# Telemetry_receiver.net
KiCad netlist of a schematic drawn in EAGLE
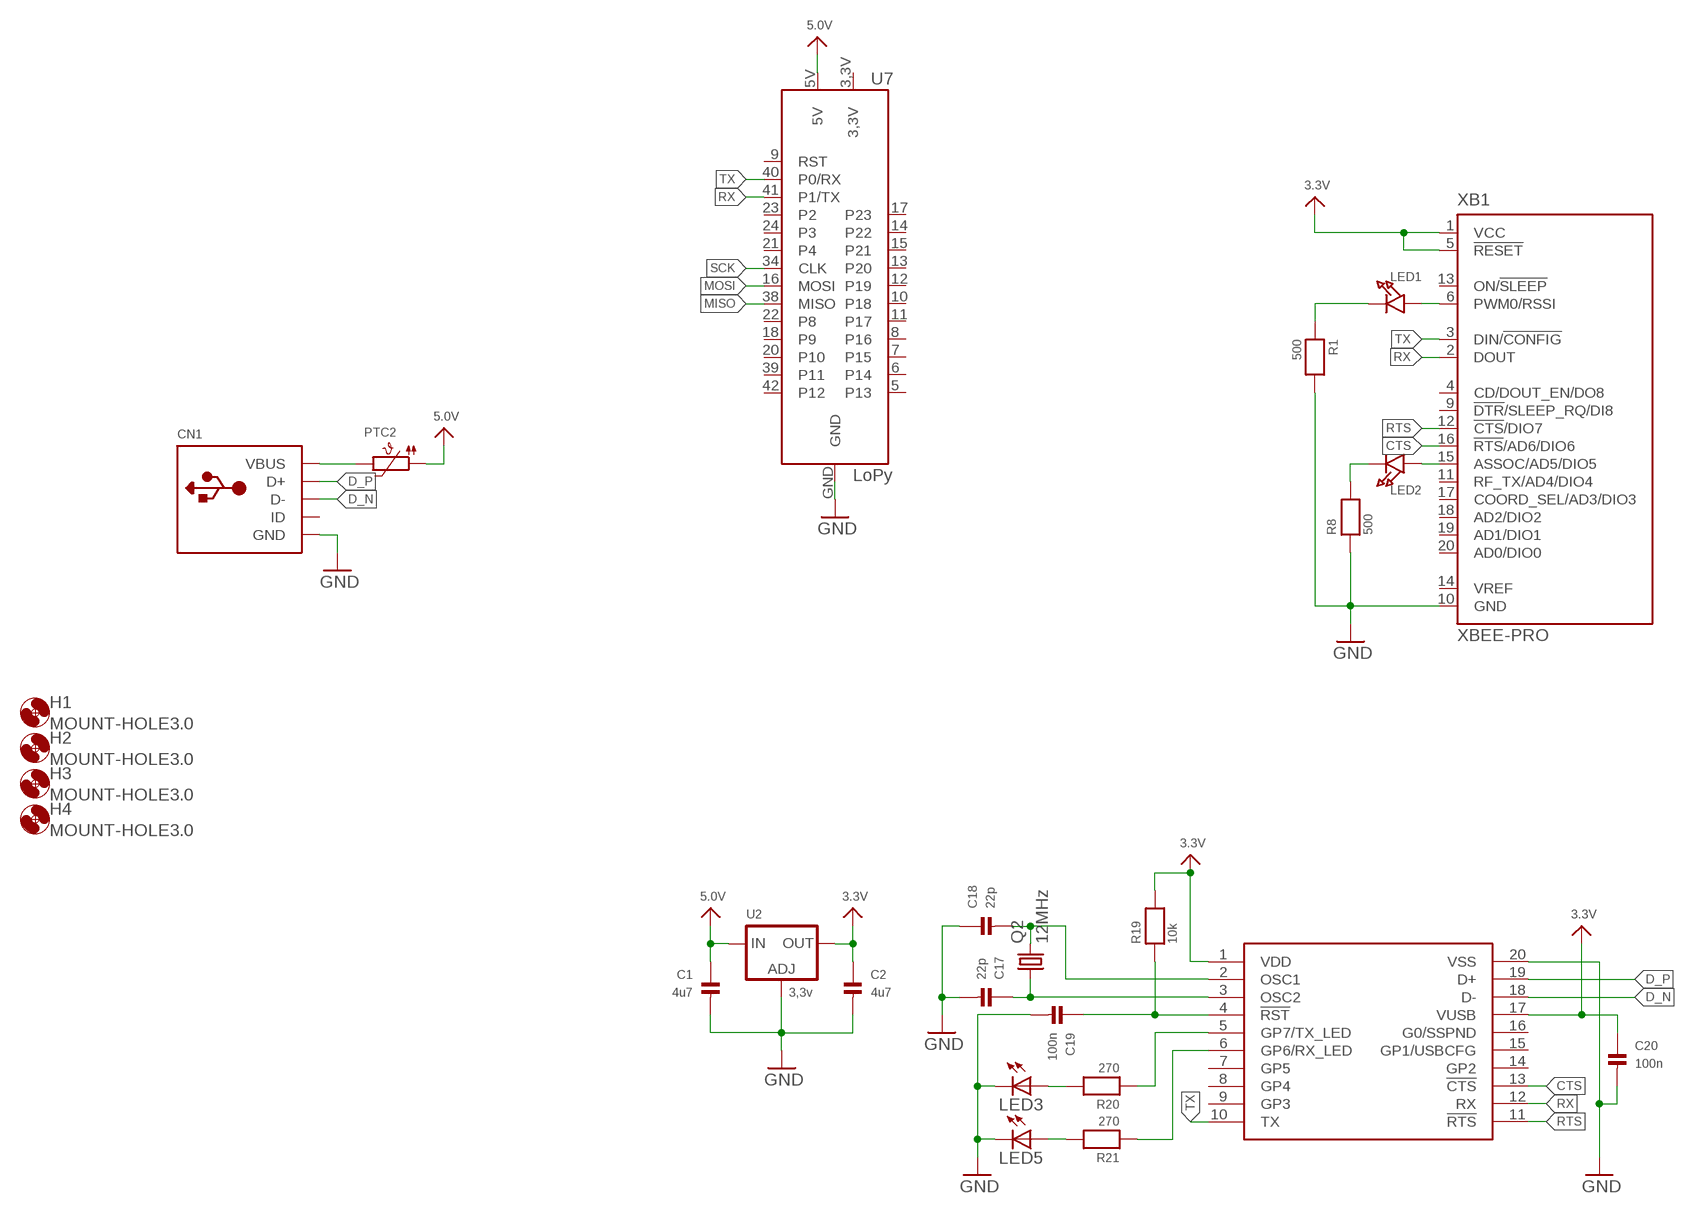
[diagram p0: schematic, sheet 1]

(export (version "E")
  (design (tool "Eeschema 10.0.6"))
  (components
    (comp (ref "C1")
      (value "4u7")
      (footprint "eagle-import:_0805")
      (libsource (lib "eagle-import") (part "CAP_CERAMIC_0805"))
    )
    (comp (ref "C2")
      (value "4u7")
      (footprint "eagle-import:_0805")
      (libsource (lib "eagle-import") (part "CAP_CERAMIC_0805"))
    )
    (comp (ref "C17")
      (value "22p")
      (footprint "eagle-import:_0603")
      (libsource (lib "eagle-import") (part "CAP_CERAMIC_0603"))
    )
    (comp (ref "C18")
      (value "22p")
      (footprint "eagle-import:_0603")
      (libsource (lib "eagle-import") (part "CAP_CERAMIC_0603"))
    )
    (comp (ref "C19")
      (value "100n")
      (footprint "eagle-import:_0603")
      (libsource (lib "eagle-import") (part "CAP_CERAMIC_0603"))
    )
    (comp (ref "C20")
      (value "100n")
      (footprint "eagle-import:_0603")
      (libsource (lib "eagle-import") (part "CAP_CERAMIC_0603"))
    )
    (comp (ref "CN1")
      (value "USBMINIBLARGE")
      (footprint "eagle-import:USB-MINIB_LARGER")
      (libsource (lib "eagle-import") (part "USBMINIBLARGE"))
    )
    (comp (ref "H1")
      (value "MOUNT-HOLE3.0")
      (footprint "eagle-import:3,0")
      (libsource (lib "eagle-import") (part "MOUNT-HOLE3.0"))
    )
    (comp (ref "H2")
      (value "MOUNT-HOLE3.0")
      (footprint "eagle-import:3,0")
      (libsource (lib "eagle-import") (part "MOUNT-HOLE3.0"))
    )
    (comp (ref "H3")
      (value "MOUNT-HOLE3.0")
      (footprint "eagle-import:3,0")
      (libsource (lib "eagle-import") (part "MOUNT-HOLE3.0"))
    )
    (comp (ref "H4")
      (value "MOUNT-HOLE3.0")
      (footprint "eagle-import:3,0")
      (libsource (lib "eagle-import") (part "MOUNT-HOLE3.0"))
    )
    (comp (ref "LED1")
      (value "LED1206")
      (footprint "eagle-import:CHIPLED_1206")
      (libsource (lib "eagle-import") (part "LED1206"))
    )
    (comp (ref "LED2")
      (value "LED1206")
      (footprint "eagle-import:CHIPLED_1206")
      (libsource (lib "eagle-import") (part "LED1206"))
    )
    (comp (ref "LED3")
      (value "LEDCHIPLED_0805")
      (footprint "eagle-import:CHIPLED_0805")
      (libsource (lib "eagle-import") (part "LEDCHIPLED_0805"))
    )
    (comp (ref "LED5")
      (value "LEDCHIPLED_0805")
      (footprint "eagle-import:CHIPLED_0805")
      (libsource (lib "eagle-import") (part "LEDCHIPLED_0805"))
    )
    (comp (ref "PTC2")
      (value "PTC1812")
      (footprint "eagle-import:PTC1812")
      (libsource (lib "eagle-import") (part "PTC1812"))
    )
    (comp (ref "Q2")
      (value "12MHz")
      (footprint "eagle-import:HC49_S")
      (libsource (lib "eagle-import") (part "CRYSTALHC49S"))
    )
    (comp (ref "R1")
      (value "500")
      (footprint "eagle-import:_0603")
      (libsource (lib "eagle-import") (part "RESISTOR_0603"))
    )
    (comp (ref "R8")
      (value "500")
      (footprint "eagle-import:_0603")
      (libsource (lib "eagle-import") (part "RESISTOR_0603"))
    )
    (comp (ref "R19")
      (value "10k")
      (footprint "eagle-import:_0603")
      (libsource (lib "eagle-import") (part "RESISTOR_0603"))
    )
    (comp (ref "R20")
      (value "270")
      (footprint "eagle-import:_0603")
      (libsource (lib "eagle-import") (part "RESISTOR_0603"))
    )
    (comp (ref "R21")
      (value "270")
      (footprint "eagle-import:_0603")
      (libsource (lib "eagle-import") (part "RESISTOR_0603"))
    )
    (comp (ref "U$24")
      (value "MCP2200")
      (footprint "eagle-import:SO20L")
      (libsource (lib "eagle-import") (part "MCP2200"))
    )
    (comp (ref "U2")
      (value "3,3v")
      (footprint "eagle-import:SOT223-R")
      (libsource (lib "eagle-import") (part "LM1117SOT223-REFLOW"))
    )
    (comp (ref "U7")
      (value "LoPy")
      (footprint "eagle-import:LOPY")
      (libsource (lib "eagle-import") (part "LOPY"))
    )
    (comp (ref "XB1")
      (value "XBEE-PRO")
      (footprint "eagle-import:XBEE-PRO")
      (fields (field (name "MPN") "XBP24-AWI-001"))
      (libsource (lib "eagle-import") (part "XBEE-PRO"))
    )
  )
  (nets
    (net (code "1") (name "3.3V") (class "Default")
      (node (ref "C2") (pin "1") (pinfunction "P$1_1") (pintype "passive"))
      (node (ref "C20") (pin "1") (pinfunction "P$1_1") (pintype "passive"))
      (node (ref "R19") (pin "2") (pinfunction "2_2") (pintype "passive"))
      (node (ref "U$24") (pin "1") (pinfunction "VDD_1") (pintype "bidirectional"))
      (node (ref "U$24") (pin "17") (pinfunction "VUSB_17") (pintype "bidirectional"))
      (node (ref "U2") (pin "2") (pinfunction "OUT_2") (pintype "passive"))
      (node (ref "XB1") (pin "1") (pinfunction "VCC_1") (pintype "power_in"))
      (node (ref "XB1") (pin "5") (pinfunction "~{RESET}_5") (pintype "input"))
    )
    (net (code "2") (name "5.0V") (class "Default")
      (node (ref "C1") (pin "1") (pinfunction "P$1_1") (pintype "passive"))
      (node (ref "PTC2") (pin "P$1") (pinfunction "1_P$1") (pintype "passive"))
      (node (ref "U2") (pin "3") (pinfunction "IN_3") (pintype "input"))
      (node (ref "U7") (pin "5V") (pinfunction "5V_5V") (pintype "bidirectional"))
    )
    (net (code "3") (name "CTS") (class "Default")
      (node (ref "U$24") (pin "13") (pinfunction "~{CTS}_13") (pintype "bidirectional"))
      (node (ref "XB1") (pin "16") (pinfunction "~{RTS}/AD6/DIO6_16") (pintype "bidirectional"))
    )
    (net (code "4") (name "D_N") (class "Default")
      (node (ref "CN1") (pin "D-") (pinfunction "D-_D-") (pintype "bidirectional"))
      (node (ref "U$24") (pin "18") (pinfunction "D-_18") (pintype "bidirectional"))
    )
    (net (code "5") (name "D_P") (class "Default")
      (node (ref "CN1") (pin "D+") (pinfunction "D+_D+") (pintype "bidirectional"))
      (node (ref "U$24") (pin "19") (pinfunction "D+_19") (pintype "bidirectional"))
    )
    (net (code "6") (name "GND") (class "Default")
      (node (ref "C1") (pin "2") (pinfunction "P$2_2") (pintype "passive"))
      (node (ref "C17") (pin "2") (pinfunction "P$2_2") (pintype "passive"))
      (node (ref "C18") (pin "1") (pinfunction "P$1_1") (pintype "passive"))
      (node (ref "C19") (pin "2") (pinfunction "P$2_2") (pintype "passive"))
      (node (ref "C2") (pin "2") (pinfunction "P$2_2") (pintype "passive"))
      (node (ref "C20") (pin "2") (pinfunction "P$2_2") (pintype "passive"))
      (node (ref "CN1") (pin "GND") (pinfunction "GND_GND") (pintype "power_in"))
      (node (ref "LED3") (pin "C") (pinfunction "C_C") (pintype "passive"))
      (node (ref "LED5") (pin "C") (pinfunction "C_C") (pintype "passive"))
      (node (ref "R1") (pin "2") (pinfunction "2_2") (pintype "passive"))
      (node (ref "R8") (pin "1") (pinfunction "1_1") (pintype "passive"))
      (node (ref "U$24") (pin "20") (pinfunction "VSS_20") (pintype "bidirectional"))
      (node (ref "U2") (pin "1") (pinfunction "ADJ_1") (pintype "input"))
      (node (ref "U7") (pin "GND") (pinfunction "GND_GND") (pintype "bidirectional"))
      (node (ref "XB1") (pin "10") (pinfunction "GND_10") (pintype "power_in"))
    )
    (net (code "7") (name "MISO") (class "Default")
      (node (ref "U7") (pin "38") (pinfunction "MISO_38") (pintype "bidirectional"))
    )
    (net (code "8") (name "MOSI") (class "Default")
      (node (ref "U7") (pin "16") (pinfunction "MOSI_16") (pintype "bidirectional"))
    )
    (net (code "9") (name "Net-(C17-P$1)") (class "Default")
      (node (ref "C17") (pin "1") (pinfunction "P$1_1") (pintype "passive"))
      (node (ref "Q2") (pin "1") (pinfunction "1_1") (pintype "passive"))
      (node (ref "U$24") (pin "3") (pinfunction "OSC2_3") (pintype "bidirectional"))
    )
    (net (code "10") (name "Net-(C18-P$2)") (class "Default")
      (node (ref "C18") (pin "2") (pinfunction "P$2_2") (pintype "passive"))
      (node (ref "Q2") (pin "2") (pinfunction "2_2") (pintype "passive"))
      (node (ref "U$24") (pin "2") (pinfunction "OSC1_2") (pintype "bidirectional"))
    )
    (net (code "11") (name "Net-(C19-P$1)") (class "Default")
      (node (ref "C19") (pin "1") (pinfunction "P$1_1") (pintype "passive"))
      (node (ref "R19") (pin "1") (pinfunction "1_1") (pintype "passive"))
      (node (ref "U$24") (pin "4") (pinfunction "~{RST}_4") (pintype "bidirectional"))
    )
    (net (code "12") (name "Net-(LED1-PadC)") (class "Default")
      (node (ref "LED1") (pin "C") (pinfunction "C_C") (pintype "passive"))
      (node (ref "R1") (pin "1") (pinfunction "1_1") (pintype "passive"))
    )
    (net (code "13") (name "Net-(LED2-PadC)") (class "Default")
      (node (ref "LED2") (pin "C") (pinfunction "C_C") (pintype "passive"))
      (node (ref "R8") (pin "2") (pinfunction "2_2") (pintype "passive"))
    )
    (net (code "14") (name "Net-(LED3-PadA)") (class "Default")
      (node (ref "LED3") (pin "A") (pinfunction "A_A") (pintype "passive"))
      (node (ref "R20") (pin "2") (pinfunction "2_2") (pintype "passive"))
    )
    (net (code "15") (name "Net-(LED5-PadA)") (class "Default")
      (node (ref "LED5") (pin "A") (pinfunction "A_A") (pintype "passive"))
      (node (ref "R21") (pin "2") (pinfunction "2_2") (pintype "passive"))
    )
    (net (code "16") (name "Net-(PTC2-2)") (class "Default")
      (node (ref "CN1") (pin "VBUS") (pinfunction "VBUS_VBUS") (pintype "power_in"))
      (node (ref "PTC2") (pin "P$2") (pinfunction "2_P$2") (pintype "passive"))
    )
    (net (code "17") (name "Net-(U$24-GP6{slash}RX_LED)") (class "Default")
      (node (ref "R21") (pin "1") (pinfunction "1_1") (pintype "passive"))
      (node (ref "U$24") (pin "6") (pinfunction "GP6/RX_LED_6") (pintype "bidirectional"))
    )
    (net (code "18") (name "Net-(U$24-GP7{slash}TX_LED)") (class "Default")
      (node (ref "R20") (pin "1") (pinfunction "1_1") (pintype "passive"))
      (node (ref "U$24") (pin "5") (pinfunction "GP7/TX_LED_5") (pintype "bidirectional"))
    )
    (net (code "19") (name "Net-(XB1-ASSOC{slash}AD5{slash}DIO5)") (class "Default")
      (node (ref "LED2") (pin "A") (pinfunction "A_A") (pintype "passive"))
      (node (ref "XB1") (pin "15") (pinfunction "ASSOC/AD5/DIO5_15") (pintype "bidirectional"))
    )
    (net (code "20") (name "Net-(XB1-PWM0{slash}RSSI)") (class "Default")
      (node (ref "LED1") (pin "A") (pinfunction "A_A") (pintype "passive"))
      (node (ref "XB1") (pin "6") (pinfunction "PWM0/RSSI_6") (pintype "output"))
    )
    (net (code "21") (name "RTS") (class "Default")
      (node (ref "U$24") (pin "11") (pinfunction "~{RTS}_11") (pintype "bidirectional"))
      (node (ref "XB1") (pin "12") (pinfunction "~{CTS}/DIO7_12") (pintype "bidirectional"))
    )
    (net (code "22") (name "RX") (class "Default")
      (node (ref "U$24") (pin "12") (pinfunction "RX_12") (pintype "bidirectional"))
      (node (ref "U7") (pin "41") (pinfunction "P1/TX_41") (pintype "bidirectional"))
      (node (ref "XB1") (pin "2") (pinfunction "DOUT_2") (pintype "output"))
    )
    (net (code "23") (name "SCK") (class "Default")
      (node (ref "U7") (pin "34") (pinfunction "CLK_34") (pintype "bidirectional"))
    )
    (net (code "24") (name "TX") (class "Default")
      (node (ref "U$24") (pin "10") (pinfunction "TX_10") (pintype "bidirectional"))
      (node (ref "U7") (pin "40") (pinfunction "P0/RX_40") (pintype "bidirectional"))
      (node (ref "XB1") (pin "3") (pinfunction "DIN/~{CONFIG}_3") (pintype "input"))
    )
    (net (code "25") (name "unconnected-(CN1-PadID)") (class "Default")
      (node (ref "CN1") (pin "ID") (pinfunction "ID_ID") (pintype "bidirectional"))
    )
    (net (code "26") (name "unconnected-(U$24-G0{slash}SSPND-Pad16)") (class "Default")
      (node (ref "U$24") (pin "16") (pinfunction "G0/SSPND_16") (pintype "bidirectional"))
    )
    (net (code "27") (name "unconnected-(U$24-GP1{slash}USBCFG-Pad15)") (class "Default")
      (node (ref "U$24") (pin "15") (pinfunction "GP1/USBCFG_15") (pintype "bidirectional"))
    )
    (net (code "28") (name "unconnected-(U$24-GP2-Pad14)") (class "Default")
      (node (ref "U$24") (pin "14") (pinfunction "GP2_14") (pintype "bidirectional"))
    )
    (net (code "29") (name "unconnected-(U$24-GP3-Pad9)") (class "Default")
      (node (ref "U$24") (pin "9") (pinfunction "GP3_9") (pintype "bidirectional"))
    )
    (net (code "30") (name "unconnected-(U$24-GP4-Pad8)") (class "Default")
      (node (ref "U$24") (pin "8") (pinfunction "GP4_8") (pintype "bidirectional"))
    )
    (net (code "31") (name "unconnected-(U$24-GP5-Pad7)") (class "Default")
      (node (ref "U$24") (pin "7") (pinfunction "GP5_7") (pintype "bidirectional"))
    )
    (net (code "32") (name "unconnected-(U7-P2-Pad23)") (class "Default")
      (node (ref "U7") (pin "23") (pinfunction "P2_23") (pintype "bidirectional"))
    )
    (net (code "33") (name "unconnected-(U7-P3-Pad24)") (class "Default")
      (node (ref "U7") (pin "24") (pinfunction "P3_24") (pintype "bidirectional"))
    )
    (net (code "34") (name "unconnected-(U7-P4-Pad21)") (class "Default")
      (node (ref "U7") (pin "21") (pinfunction "P4_21") (pintype "bidirectional"))
    )
    (net (code "35") (name "unconnected-(U7-P8-Pad22)") (class "Default")
      (node (ref "U7") (pin "22") (pinfunction "P8_22") (pintype "bidirectional"))
    )
    (net (code "36") (name "unconnected-(U7-P9-Pad18)") (class "Default")
      (node (ref "U7") (pin "18") (pinfunction "P9_18") (pintype "bidirectional"))
    )
    (net (code "37") (name "unconnected-(U7-P10-Pad20)") (class "Default")
      (node (ref "U7") (pin "20") (pinfunction "P10_20") (pintype "bidirectional"))
    )
    (net (code "38") (name "unconnected-(U7-P11-Pad39)") (class "Default")
      (node (ref "U7") (pin "39") (pinfunction "P11_39") (pintype "bidirectional"))
    )
    (net (code "39") (name "unconnected-(U7-P12-Pad42)") (class "Default")
      (node (ref "U7") (pin "42") (pinfunction "P12_42") (pintype "bidirectional"))
    )
    (net (code "40") (name "unconnected-(U7-P13-Pad5)") (class "Default")
      (node (ref "U7") (pin "5") (pinfunction "P13_5") (pintype "bidirectional"))
    )
    (net (code "41") (name "unconnected-(U7-P14-Pad6)") (class "Default")
      (node (ref "U7") (pin "6") (pinfunction "P14_6") (pintype "bidirectional"))
    )
    (net (code "42") (name "unconnected-(U7-P15-Pad7)") (class "Default")
      (node (ref "U7") (pin "7") (pinfunction "P15_7") (pintype "bidirectional"))
    )
    (net (code "43") (name "unconnected-(U7-P16-Pad8)") (class "Default")
      (node (ref "U7") (pin "8") (pinfunction "P16_8") (pintype "bidirectional"))
    )
    (net (code "44") (name "unconnected-(U7-P17-Pad11)") (class "Default")
      (node (ref "U7") (pin "11") (pinfunction "P17_11") (pintype "bidirectional"))
    )
    (net (code "45") (name "unconnected-(U7-P18-Pad10)") (class "Default")
      (node (ref "U7") (pin "10") (pinfunction "P18_10") (pintype "bidirectional"))
    )
    (net (code "46") (name "unconnected-(U7-P19-Pad12)") (class "Default")
      (node (ref "U7") (pin "12") (pinfunction "P19_12") (pintype "bidirectional"))
    )
    (net (code "47") (name "unconnected-(U7-P20-Pad13)") (class "Default")
      (node (ref "U7") (pin "13") (pinfunction "P20_13") (pintype "bidirectional"))
    )
    (net (code "48") (name "unconnected-(U7-P21-Pad15)") (class "Default")
      (node (ref "U7") (pin "15") (pinfunction "P21_15") (pintype "bidirectional"))
    )
    (net (code "49") (name "unconnected-(U7-P22-Pad14)") (class "Default")
      (node (ref "U7") (pin "14") (pinfunction "P22_14") (pintype "bidirectional"))
    )
    (net (code "50") (name "unconnected-(U7-P23-Pad17)") (class "Default")
      (node (ref "U7") (pin "17") (pinfunction "P23_17") (pintype "bidirectional"))
    )
    (net (code "51") (name "unconnected-(U7-Pad3,3V)") (class "Default")
      (node (ref "U7") (pin "3,3V") (pinfunction "3,3V_3,3V") (pintype "bidirectional"))
    )
    (net (code "52") (name "unconnected-(U7-RST-Pad9)") (class "Default")
      (node (ref "U7") (pin "9") (pinfunction "RST_9") (pintype "bidirectional"))
    )
    (net (code "53") (name "unconnected-(XB1-AD0{slash}DIO0-Pad20)") (class "Default")
      (node (ref "XB1") (pin "20") (pinfunction "AD0/DIO0_20") (pintype "bidirectional"))
    )
    (net (code "54") (name "unconnected-(XB1-AD1{slash}DIO1-Pad19)") (class "Default")
      (node (ref "XB1") (pin "19") (pinfunction "AD1/DIO1_19") (pintype "bidirectional"))
    )
    (net (code "55") (name "unconnected-(XB1-AD2{slash}DIO2-Pad18)") (class "Default")
      (node (ref "XB1") (pin "18") (pinfunction "AD2/DIO2_18") (pintype "bidirectional"))
    )
    (net (code "56") (name "unconnected-(XB1-CD{slash}DOUT_EN{slash}DO8-Pad4)") (class "Default")
      (node (ref "XB1") (pin "4") (pinfunction "CD/DOUT_EN/DO8_4") (pintype "output"))
    )
    (net (code "57") (name "unconnected-(XB1-COORD_SEL{slash}AD3{slash}DIO3-Pad17)") (class "Default")
      (node (ref "XB1") (pin "17") (pinfunction "COORD_SEL/AD3/DIO3_17") (pintype "bidirectional"))
    )
    (net (code "58") (name "unconnected-(XB1-ON{slash}~{SLEEP}-Pad13)") (class "Default")
      (node (ref "XB1") (pin "13") (pinfunction "ON/~{SLEEP}_13") (pintype "output"))
    )
    (net (code "59") (name "unconnected-(XB1-RF_TX{slash}AD4{slash}DIO4-Pad11)") (class "Default")
      (node (ref "XB1") (pin "11") (pinfunction "RF_TX/AD4/DIO4_11") (pintype "bidirectional"))
    )
    (net (code "60") (name "unconnected-(XB1-VREF-Pad14)") (class "Default")
      (node (ref "XB1") (pin "14") (pinfunction "VREF_14") (pintype "input"))
    )
    (net (code "61") (name "unconnected-(XB1-~{DTR}{slash}SLEEP_RQ{slash}DI8-Pad9)") (class "Default")
      (node (ref "XB1") (pin "9") (pinfunction "~{DTR}/SLEEP_RQ/DI8_9") (pintype "bidirectional"))
    )
  )
)
